# focuser-no-jumper.net
KiCad netlist of a schematic drawn in EAGLE
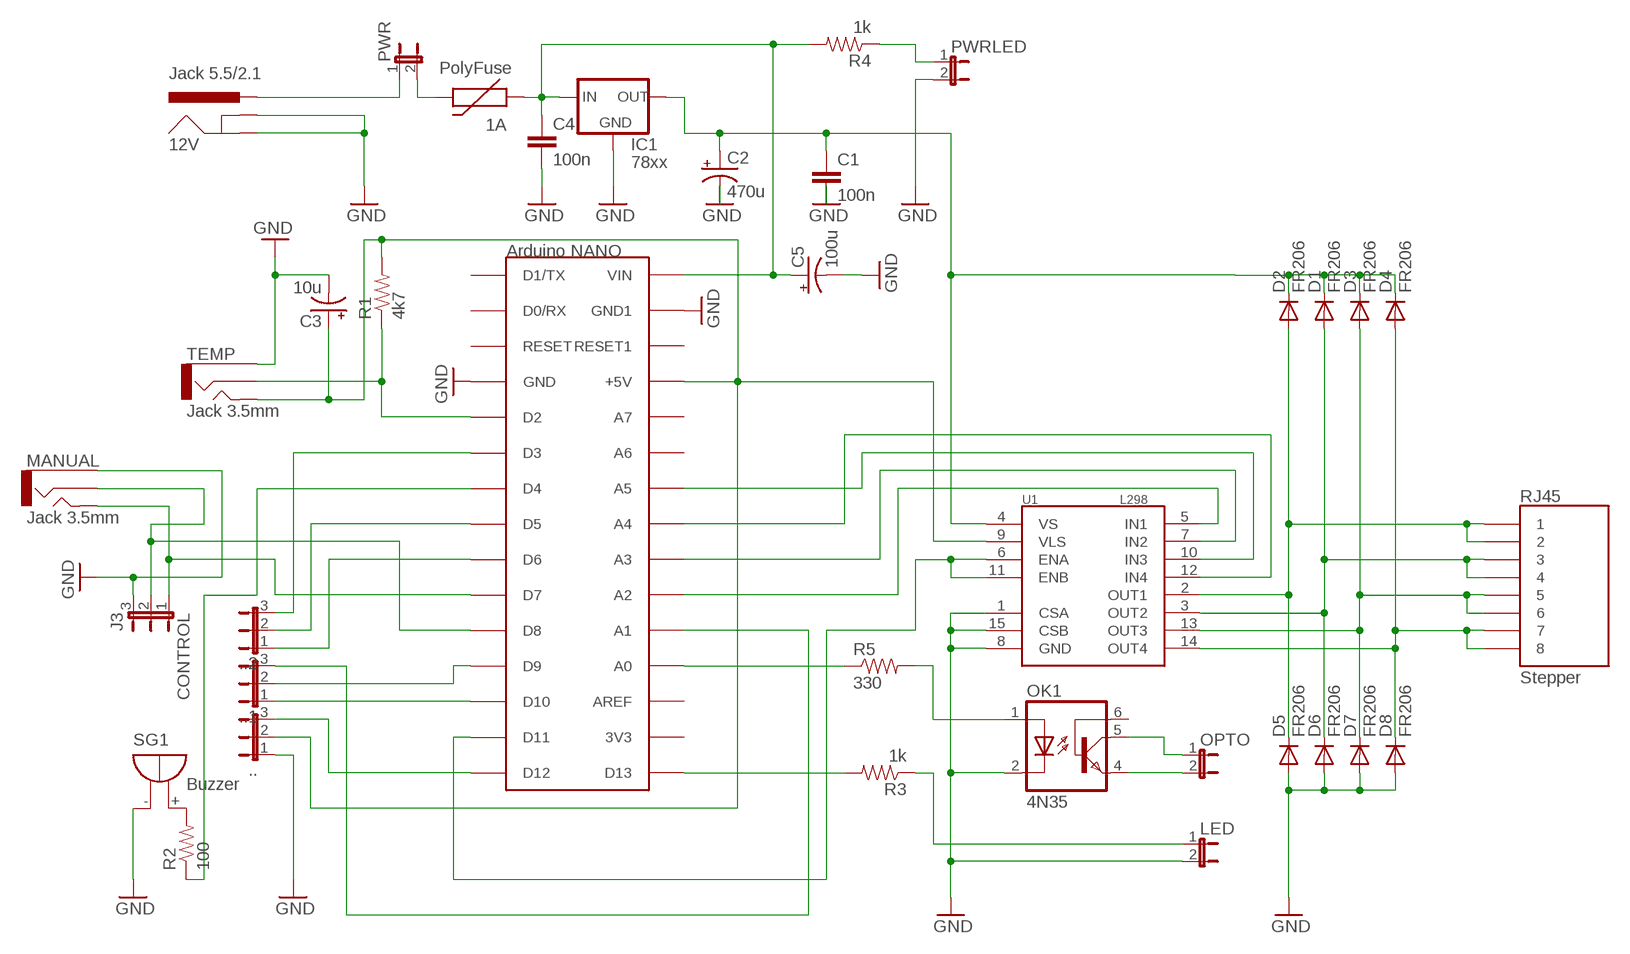
[diagram p0: schematic, sheet 1]

(export (version "E")
  (design (tool "Eeschema 10.0.6"))
  (components
    (comp (ref "..")
      (value "JUMPER-3PTH")
      (footprint "eagle-import:1X03")
      (libsource (lib "eagle-import") (part "JUMPER-3PTH"))
    )
    (comp (ref "..1")
      (value "JUMPER-3PTH")
      (footprint "eagle-import:1X03")
      (libsource (lib "eagle-import") (part "JUMPER-3PTH"))
    )
    (comp (ref "..2")
      (value "JUMPER-3PTH")
      (footprint "eagle-import:1X03")
      (libsource (lib "eagle-import") (part "JUMPER-3PTH"))
    )
    (comp (ref "1A")
      (value "PolyFuse")
      (footprint "eagle-import:PTC")
      (libsource (lib "eagle-import") (part "PTCPTH"))
    )
    (comp (ref "12V")
      (value "Jack 5.5/2.1")
      (footprint "eagle-import:POWER_JACK_COMBO")
      (libsource (lib "eagle-import") (part "POWER_JACKCOMBO"))
    )
    (comp (ref "C1")
      (value "100n")
      (footprint "eagle-import:AXIAL-5MM")
      (libsource (lib "eagle-import") (part "CAP_"))
    )
    (comp (ref "C2")
      (value "470u")
      (footprint "eagle-import:CPOL-RADIAL-100UF-25V")
      (libsource (lib "eagle-import") (part "CAP_POLPTH1"))
    )
    (comp (ref "C3")
      (value "10u")
      (footprint "eagle-import:CPOL-RADIAL-100UF-25V")
      (libsource (lib "eagle-import") (part "CAP_POLPTH1"))
    )
    (comp (ref "C4")
      (value "100n")
      (footprint "eagle-import:AXIAL-5MM")
      (libsource (lib "eagle-import") (part "CAP_"))
    )
    (comp (ref "C5")
      (value "100u")
      (footprint "eagle-import:CPOL-RADIAL-100UF-25V")
      (libsource (lib "eagle-import") (part "CAP_POLPTH1"))
    )
    (comp (ref "CONTROL")
      (value "J3")
      (footprint "eagle-import:1X03")
      (libsource (lib "eagle-import") (part "JUMPER-3PTH"))
    )
    (comp (ref "D1")
      (value "FR206")
      (footprint "eagle-import:DO41-10")
      (libsource (lib "eagle-import") (part "1N4004"))
    )
    (comp (ref "D2")
      (value "FR206")
      (footprint "eagle-import:DO41-10")
      (libsource (lib "eagle-import") (part "1N4004"))
    )
    (comp (ref "D3")
      (value "FR206")
      (footprint "eagle-import:DIODE-1N4001")
      (libsource (lib "eagle-import") (part "DIODEPTH"))
    )
    (comp (ref "D4")
      (value "FR206")
      (footprint "eagle-import:DIODE-1N4001")
      (libsource (lib "eagle-import") (part "DIODEPTH"))
    )
    (comp (ref "D5")
      (value "FR206")
      (footprint "eagle-import:DIODE-1N4001")
      (libsource (lib "eagle-import") (part "DIODEPTH"))
    )
    (comp (ref "D6")
      (value "FR206")
      (footprint "eagle-import:DIODE-1N4001")
      (libsource (lib "eagle-import") (part "DIODEPTH"))
    )
    (comp (ref "D7")
      (value "FR206")
      (footprint "eagle-import:DIODE-1N4001")
      (libsource (lib "eagle-import") (part "DIODEPTH"))
    )
    (comp (ref "D8")
      (value "FR206")
      (footprint "eagle-import:DIODE-1N4001")
      (libsource (lib "eagle-import") (part "DIODEPTH"))
    )
    (comp (ref "IC1")
      (value "78xx")
      (footprint "eagle-import:TO220-IGO")
      (libsource (lib "eagle-import") (part "V_REG_78XXSINK"))
    )
    (comp (ref "LED")
      (value "JUMPER-2PTH")
      (footprint "eagle-import:1X02")
      (libsource (lib "eagle-import") (part "JUMPER-2PTH"))
    )
    (comp (ref "MANUAL")
      (value "Jack 3.5mm")
      (footprint "eagle-import:AUDIO-JACK")
      (libsource (lib "eagle-import") (part "AUDIO-JACKPTH"))
    )
    (comp (ref "NANO")
      (value "MMduino")
      (footprint "eagle-import:PDIP-32")
      (fields (field (name "NAM") "Arduino NANO"))
      (libsource (lib "eagle-import") (part "ARDUINONANO"))
    )
    (comp (ref "OK1")
      (value "4N35")
      (footprint "eagle-import:DIL06")
      (fields (field (name "MF") "FAIRCHILD SEMICONDUCTOR"))
      (libsource (lib "eagle-import") (part "4N35"))
    )
    (comp (ref "OPTO")
      (value "JUMPER-2PTH")
      (footprint "eagle-import:1X02")
      (libsource (lib "eagle-import") (part "JUMPER-2PTH"))
    )
    (comp (ref "PWR")
      (value "JUMPER-2PTH")
      (footprint "eagle-import:1X02")
      (libsource (lib "eagle-import") (part "JUMPER-2PTH"))
    )
    (comp (ref "PWRLED")
      (value "JUMPER-2PTH")
      (footprint "eagle-import:1X02")
      (libsource (lib "eagle-import") (part "JUMPER-2PTH"))
    )
    (comp (ref "R1")
      (value "4k7")
      (footprint "eagle-import:AXIAL-0.3")
      (libsource (lib "eagle-import") (part "RESISTORPTH1"))
    )
    (comp (ref "R2")
      (value "100")
      (footprint "eagle-import:AXIAL-0.3")
      (libsource (lib "eagle-import") (part "RESISTORPTH1"))
    )
    (comp (ref "R3")
      (value "1k")
      (footprint "eagle-import:AXIAL-0.3")
      (libsource (lib "eagle-import") (part "RESISTORPTH1"))
    )
    (comp (ref "R4")
      (value "1k")
      (footprint "eagle-import:AXIAL-0.3")
      (libsource (lib "eagle-import") (part "RESISTORPTH1"))
    )
    (comp (ref "R5")
      (value "330")
      (footprint "eagle-import:AXIAL-0.3")
      (libsource (lib "eagle-import") (part "RESISTORPTH1"))
    )
    (comp (ref "RJ45")
      (value "Stepper")
      (footprint "eagle-import:RJ45-8")
      (libsource (lib "eagle-import") (part "RJ45-8PTH"))
    )
    (comp (ref "SG1")
      (value "Buzzer")
      (footprint "eagle-import:F_QMBIII")
      (libsource (lib "eagle-import") (part "F/QMBIII"))
    )
    (comp (ref "TEMP")
      (value "Jack 3.5mm")
      (footprint "eagle-import:AUDIO-JACK")
      (libsource (lib "eagle-import") (part "AUDIO-JACKPTH"))
    )
    (comp (ref "U1")
      (value "L298")
      (footprint "eagle-import:MULTIWATT15")
      (libsource (lib "eagle-import") (part "L298"))
    )
  )
  (nets
    (net (code "1") (name "GND") (class "Default")
      (node (ref "..") (pin "1") (pinfunction "1_1") (pintype "passive"))
      (node (ref "12V") (pin "GND") (pinfunction "GNDBREAK_GND") (pintype "bidirectional"))
      (node (ref "12V") (pin "GND@1") (pinfunction "GND_GND@1") (pintype "bidirectional"))
      (node (ref "C1") (pin "P$2") (pinfunction "2_P$2") (pintype "passive"))
      (node (ref "C2") (pin "2") (pinfunction "-_2") (pintype "passive"))
      (node (ref "C3") (pin "2") (pinfunction "-_2") (pintype "passive"))
      (node (ref "C4") (pin "P$2") (pinfunction "2_P$2") (pintype "passive"))
      (node (ref "C5") (pin "2") (pinfunction "-_2") (pintype "passive"))
      (node (ref "CONTROL") (pin "3") (pinfunction "3_3") (pintype "passive"))
      (node (ref "D5") (pin "A") (pinfunction "A_A") (pintype "passive"))
      (node (ref "D6") (pin "A") (pinfunction "A_A") (pintype "passive"))
      (node (ref "D7") (pin "A") (pinfunction "A_A") (pintype "passive"))
      (node (ref "D8") (pin "A") (pinfunction "A_A") (pintype "passive"))
      (node (ref "IC1") (pin "GND") (pinfunction "GND_GND") (pintype "input"))
      (node (ref "LED") (pin "2") (pinfunction "2_2") (pintype "passive"))
      (node (ref "MANUAL") (pin "1") (pinfunction "1_1") (pintype "bidirectional"))
      (node (ref "NANO") (pin "GND") (pinfunction "GND_GND") (pintype "bidirectional"))
      (node (ref "NANO") (pin "GND1") (pinfunction "GND1_GND1") (pintype "bidirectional"))
      (node (ref "OK1") (pin "2") (pinfunction "C_2") (pintype "passive"))
      (node (ref "PWRLED") (pin "2") (pinfunction "2_2") (pintype "passive"))
      (node (ref "SG1") (pin "-") (pinfunction "+_-") (pintype "passive"))
      (node (ref "TEMP") (pin "1") (pinfunction "1_1") (pintype "bidirectional"))
      (node (ref "U1") (pin "1") (pinfunction "CSA_1") (pintype "bidirectional"))
      (node (ref "U1") (pin "15") (pinfunction "CSB_15") (pintype "bidirectional"))
      (node (ref "U1") (pin "8") (pinfunction "GND_8") (pintype "bidirectional"))
    )
    (net (code "2") (name "Net-(..-Pad3)") (class "Default")
      (node (ref "..") (pin "3") (pinfunction "3_3") (pintype "passive"))
      (node (ref "NANO") (pin "D12") (pinfunction "D12_D12") (pintype "bidirectional"))
    )
    (net (code "3") (name "Net-(..1-Pad1)") (class "Default")
      (node (ref "..1") (pin "1") (pinfunction "1_1") (pintype "passive"))
      (node (ref "NANO") (pin "D10") (pinfunction "D10_D10") (pintype "bidirectional"))
    )
    (net (code "4") (name "Net-(..1-Pad2)") (class "Default")
      (node (ref "..1") (pin "2") (pinfunction "2_2") (pintype "passive"))
      (node (ref "NANO") (pin "D9") (pinfunction "D9_D9") (pintype "bidirectional"))
    )
    (net (code "5") (name "Net-(..2-Pad1)") (class "Default")
      (node (ref "..2") (pin "1") (pinfunction "1_1") (pintype "passive"))
      (node (ref "NANO") (pin "D6") (pinfunction "D6_D6") (pintype "bidirectional"))
    )
    (net (code "6") (name "Net-(..2-Pad2)") (class "Default")
      (node (ref "..2") (pin "2") (pinfunction "2_2") (pintype "passive"))
      (node (ref "NANO") (pin "D5") (pinfunction "D5_D5") (pintype "bidirectional"))
    )
    (net (code "7") (name "Net-(..2-Pad3)") (class "Default")
      (node (ref "..2") (pin "3") (pinfunction "3_3") (pintype "passive"))
      (node (ref "NANO") (pin "D3") (pinfunction "D3_D3") (pintype "bidirectional"))
    )
    (net (code "8") (name "Net-(1A-1)") (class "Default")
      (node (ref "1A") (pin "P$1") (pinfunction "1_P$1") (pintype "bidirectional"))
      (node (ref "C4") (pin "P$1") (pinfunction "1_P$1") (pintype "passive"))
      (node (ref "C5") (pin "1") (pinfunction "+_1") (pintype "passive"))
      (node (ref "IC1") (pin "IN") (pinfunction "IN_IN") (pintype "input"))
      (node (ref "NANO") (pin "VIN") (pinfunction "VIN_VIN") (pintype "bidirectional"))
      (node (ref "R4") (pin "P$2") (pinfunction "2_P$2") (pintype "passive"))
    )
    (net (code "9") (name "Net-(1A-2)") (class "Default")
      (node (ref "1A") (pin "P$2") (pinfunction "2_P$2") (pintype "bidirectional"))
      (node (ref "PWR") (pin "2") (pinfunction "2_2") (pintype "passive"))
    )
    (net (code "10") (name "Net-(12V-PWR)") (class "Default")
      (node (ref "12V") (pin "POWER") (pinfunction "PWR_POWER") (pintype "bidirectional"))
      (node (ref "PWR") (pin "1") (pinfunction "1_1") (pintype "passive"))
    )
    (net (code "11") (name "Net-(C1-1)") (class "Default")
      (node (ref "C1") (pin "P$1") (pinfunction "1_P$1") (pintype "passive"))
      (node (ref "C2") (pin "1") (pinfunction "+_1") (pintype "passive"))
      (node (ref "D1") (pin "C") (pinfunction "C_C") (pintype "passive"))
      (node (ref "D2") (pin "C") (pinfunction "C_C") (pintype "passive"))
      (node (ref "D3") (pin "C") (pinfunction "C_C") (pintype "passive"))
      (node (ref "D4") (pin "C") (pinfunction "C_C") (pintype "passive"))
      (node (ref "IC1") (pin "OUT") (pinfunction "OUT_OUT") (pintype "output"))
      (node (ref "U1") (pin "4") (pinfunction "VS_4") (pintype "bidirectional"))
    )
    (net (code "12") (name "Net-(C3-+)") (class "Default")
      (node (ref "..") (pin "2") (pinfunction "2_2") (pintype "passive"))
      (node (ref "C3") (pin "1") (pinfunction "+_1") (pintype "passive"))
      (node (ref "NANO") (pin "+5V") (pinfunction "+5V_+5V") (pintype "bidirectional"))
      (node (ref "R1") (pin "P$2") (pinfunction "2_P$2") (pintype "passive"))
      (node (ref "TEMP") (pin "5") (pinfunction "5_5") (pintype "bidirectional"))
      (node (ref "U1") (pin "9") (pinfunction "VLS_9") (pintype "bidirectional"))
    )
    (net (code "13") (name "Net-(CONTROL-Pad1)") (class "Default")
      (node (ref "CONTROL") (pin "1") (pinfunction "1_1") (pintype "passive"))
      (node (ref "MANUAL") (pin "5") (pinfunction "5_5") (pintype "bidirectional"))
      (node (ref "NANO") (pin "D7") (pinfunction "D7_D7") (pintype "bidirectional"))
    )
    (net (code "14") (name "Net-(CONTROL-Pad2)") (class "Default")
      (node (ref "CONTROL") (pin "2") (pinfunction "2_2") (pintype "passive"))
      (node (ref "MANUAL") (pin "2") (pinfunction "2_2") (pintype "bidirectional"))
      (node (ref "NANO") (pin "D8") (pinfunction "D8_D8") (pintype "bidirectional"))
    )
    (net (code "15") (name "Net-(NANO-A0)") (class "Default")
      (node (ref "NANO") (pin "A7") (pinfunction "A0_A7") (pintype "bidirectional"))
      (node (ref "R5") (pin "P$1") (pinfunction "1_P$1") (pintype "passive"))
    )
    (net (code "16") (name "Net-(NANO-A1)") (class "Default")
      (node (ref "..1") (pin "3") (pinfunction "3_3") (pintype "passive"))
      (node (ref "NANO") (pin "A6") (pinfunction "A1_A6") (pintype "bidirectional"))
    )
    (net (code "17") (name "Net-(NANO-A2)") (class "Default")
      (node (ref "NANO") (pin "A5") (pinfunction "A2_A5") (pintype "bidirectional"))
      (node (ref "U1") (pin "5") (pinfunction "IN1_5") (pintype "bidirectional"))
    )
    (net (code "18") (name "Net-(NANO-A3)") (class "Default")
      (node (ref "NANO") (pin "A4") (pinfunction "A3_A4") (pintype "bidirectional"))
      (node (ref "U1") (pin "7") (pinfunction "IN2_7") (pintype "bidirectional"))
    )
    (net (code "19") (name "Net-(NANO-A4)") (class "Default")
      (node (ref "NANO") (pin "A3") (pinfunction "A4_A3") (pintype "bidirectional"))
      (node (ref "U1") (pin "12") (pinfunction "IN4_12") (pintype "bidirectional"))
    )
    (net (code "20") (name "Net-(NANO-A5)") (class "Default")
      (node (ref "NANO") (pin "A2") (pinfunction "A5_A2") (pintype "bidirectional"))
      (node (ref "U1") (pin "10") (pinfunction "IN3_10") (pintype "bidirectional"))
    )
    (net (code "21") (name "Net-(OK1-A)") (class "Default")
      (node (ref "OK1") (pin "1") (pinfunction "A_1") (pintype "passive"))
      (node (ref "R5") (pin "P$2") (pinfunction "2_P$2") (pintype "passive"))
    )
    (net (code "22") (name "Net-(OK1-COL)") (class "Default")
      (node (ref "OK1") (pin "5") (pinfunction "COL_5") (pintype "passive"))
      (node (ref "OPTO") (pin "1") (pinfunction "1_1") (pintype "passive"))
    )
    (net (code "23") (name "Net-(OK1-EMI)") (class "Default")
      (node (ref "OK1") (pin "4") (pinfunction "EMI_4") (pintype "passive"))
      (node (ref "OPTO") (pin "2") (pinfunction "2_2") (pintype "passive"))
    )
    (net (code "24") (name "Net-(R1-1)") (class "Default")
      (node (ref "NANO") (pin "D2") (pinfunction "D2_D2") (pintype "bidirectional"))
      (node (ref "R1") (pin "P$1") (pinfunction "1_P$1") (pintype "passive"))
      (node (ref "TEMP") (pin "2") (pinfunction "2_2") (pintype "bidirectional"))
    )
    (net (code "25") (name "Net-(R2-1)") (class "Default")
      (node (ref "NANO") (pin "D4") (pinfunction "D4_D4") (pintype "bidirectional"))
      (node (ref "R2") (pin "P$1") (pinfunction "1_P$1") (pintype "passive"))
    )
    (net (code "26") (name "Net-(R2-2)") (class "Default")
      (node (ref "R2") (pin "P$2") (pinfunction "2_P$2") (pintype "passive"))
      (node (ref "SG1") (pin "+") (pinfunction "-_+") (pintype "passive"))
    )
    (net (code "27") (name "Net-(R3-1)") (class "Default")
      (node (ref "LED") (pin "1") (pinfunction "1_1") (pintype "passive"))
      (node (ref "R3") (pin "P$1") (pinfunction "1_P$1") (pintype "passive"))
    )
    (net (code "28") (name "Net-(R3-2)") (class "Default")
      (node (ref "NANO") (pin "D13") (pinfunction "D13_D13") (pintype "bidirectional"))
      (node (ref "R3") (pin "P$2") (pinfunction "2_P$2") (pintype "passive"))
    )
    (net (code "29") (name "Net-(R4-1)") (class "Default")
      (node (ref "PWRLED") (pin "1") (pinfunction "1_1") (pintype "passive"))
      (node (ref "R4") (pin "P$1") (pinfunction "1_P$1") (pintype "passive"))
    )
    (net (code "30") (name "Net-(U1-ENA)") (class "Default")
      (node (ref "NANO") (pin "D11") (pinfunction "D11_D11") (pintype "bidirectional"))
      (node (ref "U1") (pin "11") (pinfunction "ENB_11") (pintype "bidirectional"))
      (node (ref "U1") (pin "6") (pinfunction "ENA_6") (pintype "bidirectional"))
    )
    (net (code "31") (name "Net-(U1-OUT1)") (class "Default")
      (node (ref "D2") (pin "A") (pinfunction "A_A") (pintype "passive"))
      (node (ref "D5") (pin "C") (pinfunction "C_C") (pintype "passive"))
      (node (ref "RJ45") (pin "1") (pinfunction "1_1") (pintype "bidirectional"))
      (node (ref "RJ45") (pin "2") (pinfunction "2_2") (pintype "bidirectional"))
      (node (ref "U1") (pin "2") (pinfunction "OUT1_2") (pintype "bidirectional"))
    )
    (net (code "32") (name "Net-(U1-OUT2)") (class "Default")
      (node (ref "D1") (pin "A") (pinfunction "A_A") (pintype "passive"))
      (node (ref "D6") (pin "C") (pinfunction "C_C") (pintype "passive"))
      (node (ref "RJ45") (pin "3") (pinfunction "3_3") (pintype "bidirectional"))
      (node (ref "RJ45") (pin "4") (pinfunction "4_4") (pintype "bidirectional"))
      (node (ref "U1") (pin "3") (pinfunction "OUT2_3") (pintype "bidirectional"))
    )
    (net (code "33") (name "Net-(U1-OUT3)") (class "Default")
      (node (ref "D3") (pin "A") (pinfunction "A_A") (pintype "passive"))
      (node (ref "D7") (pin "C") (pinfunction "C_C") (pintype "passive"))
      (node (ref "RJ45") (pin "5") (pinfunction "5_5") (pintype "bidirectional"))
      (node (ref "RJ45") (pin "6") (pinfunction "6_6") (pintype "bidirectional"))
      (node (ref "U1") (pin "13") (pinfunction "OUT3_13") (pintype "bidirectional"))
    )
    (net (code "34") (name "Net-(U1-OUT4)") (class "Default")
      (node (ref "D4") (pin "A") (pinfunction "A_A") (pintype "passive"))
      (node (ref "D8") (pin "C") (pinfunction "C_C") (pintype "passive"))
      (node (ref "RJ45") (pin "7") (pinfunction "7_7") (pintype "bidirectional"))
      (node (ref "RJ45") (pin "8") (pinfunction "8_8") (pintype "bidirectional"))
      (node (ref "U1") (pin "14") (pinfunction "OUT4_14") (pintype "bidirectional"))
    )
    (net (code "35") (name "unconnected-(NANO-A6-PadA1)") (class "Default")
      (node (ref "NANO") (pin "A1") (pinfunction "A6_A1") (pintype "bidirectional"))
    )
    (net (code "36") (name "unconnected-(NANO-A7-PadA0)") (class "Default")
      (node (ref "NANO") (pin "A0") (pinfunction "A7_A0") (pintype "bidirectional"))
    )
    (net (code "37") (name "unconnected-(NANO-Pad3V3)") (class "Default")
      (node (ref "NANO") (pin "3V3") (pinfunction "3V3_3V3") (pintype "bidirectional"))
    )
    (net (code "38") (name "unconnected-(NANO-PadAREF)") (class "Default")
      (node (ref "NANO") (pin "AREF") (pinfunction "AREF_AREF") (pintype "bidirectional"))
    )
    (net (code "39") (name "unconnected-(NANO-PadD0{slash}RX)") (class "Default")
      (node (ref "NANO") (pin "D0/RX") (pinfunction "D0/RX_D0/RX") (pintype "bidirectional"))
    )
    (net (code "40") (name "unconnected-(NANO-PadD1{slash}TX)") (class "Default")
      (node (ref "NANO") (pin "D1/TX") (pinfunction "D1/TX_D1/TX") (pintype "bidirectional"))
    )
    (net (code "41") (name "unconnected-(NANO-PadRESET)") (class "Default")
      (node (ref "NANO") (pin "RESET") (pinfunction "RESET_RESET") (pintype "bidirectional"))
    )
    (net (code "42") (name "unconnected-(NANO-PadRESET1)") (class "Default")
      (node (ref "NANO") (pin "RESET1") (pinfunction "RESET1_RESET1") (pintype "bidirectional"))
    )
    (net (code "43") (name "unconnected-(OK1-BAS-Pad6)") (class "Default")
      (node (ref "OK1") (pin "6") (pinfunction "BAS_6") (pintype "passive"))
    )
  )
)
